# TPS_secondary_wiper.net
KiCad netlist of a schematic drawn in Altium Designer
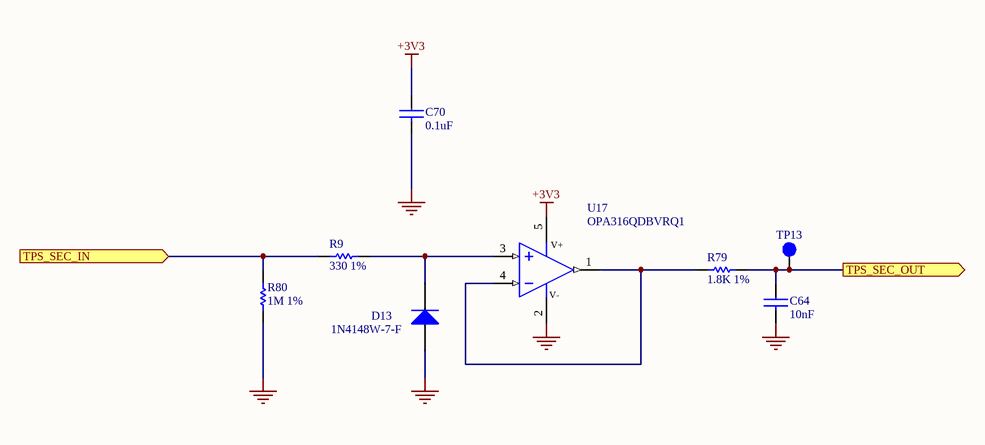
[diagram p0: TPS_secondary_wiper.SchDoc]

(export (version "E")
  (design (tool "Eeschema 10.0.6"))
  (components
    (comp (ref "C64")
      (value "10nF")
      (footprint "C0805")
      (fields
        (field (name "MANUFACTURER") "Yageo")
        (field (name "MANUFACTURER PART NUMBER") "CC0805KRX7R9BB103")
        (field (name "TOLERANCE") "10%")
      )
      (libsource (lib "MCx") (part "CC0805KRX7R9BB103"))
    )
    (comp (ref "C70")
      (value "0.1uF")
      (footprint "C0805")
      (description "Cap Ceramic 0.1uF 50V X7R 10% SMD 2.0 x 1.2 mm 125 C Paper T/R")
      (fields
        (field (name "MANUFACTURER") "KEMET")
        (field (name "MANUFACTURER PART NUMBER") "C0805C104K5RACTU")
      )
      (libsource (lib "MCx") (part "C0805C104K5RACTU"))
    )
    (comp (ref "D13")
      (value "1N4148W-7-F")
      (footprint "MC1:DIOD-SOD123-2_V")
      (description "DIODE GEN PURP 100V 300MA SOD123")
      (fields (field (name "MANUFACTURER") "Diodes") (field (name "VOLTAGE") "100V"))
      (libsource (lib "MC1") (part "1N4148W-7-F"))
    )
    (comp (ref "R9")
      (value "330 1%")
      (footprint "R0805")
      (description "RES SMD 330 OHM 1% 1/8W 0805")
      (fields
        (field (name "MANUFACTURER") "Panasonic")
        (field (name "MANUFACTURER PART NUMBER") "ERJ-6ENF3300V")
      )
      (libsource (lib "MCx") (part "ERJ-6ENF3300V"))
    )
    (comp (ref "R79")
      (value "1.8K 1%")
      (footprint "R0805")
      (description "RESISTOR, 0805, 0.125W, 1%, 1K8")
      (fields
        (field (name "MANUFACTURER") "Panasonic")
        (field (name "MANUFACTURER PART NUMBER") "ERJ-6ENF1801V")
      )
      (libsource (lib "MCx") (part "ERJ-6ENF1801V"))
    )
    (comp (ref "R80")
      (value "1M 1%")
      (footprint "R0805")
      (description "Res Thick Film 0805 1M Ohm 1% 1/8W 100ppm/C Molded SMD Punched Carrier T/R")
      (fields
        (field (name "MANUFACTURER") "Panasonic")
        (field (name "MANUFACTURER PART NUMBER") "ERJ-6ENF1004V")
      )
      (libsource (lib "MCx") (part "ERJ-6ENF1004V"))
    )
    (comp (ref "TP13")
      (value "T")
      (footprint "MC1:TESTPOINTSMD_1x1MM")
      (description "SMD Test Point")
      (libsource (lib "MC1") (part "TestPoint_SMD_1x1"))
    )
    (comp (ref "U17")
      (value "OPA316QDBVRQ1")
      (footprint "DBV0005A_M")
      (description "Op Amp Single Low Power Amplifier R-R I/O ±2.75V/5.5V Automotive 5-Pin SOT-23 T/R")
      (fields (field (name "MANUFACTURER") "Texas Instruments"))
      (libsource (lib "MCx") (part "OPA316QDBVRQ1"))
    )
  )
  (nets
    (net (code "1") (name "+3V3") (class "Default")
      (node (ref "C70") (pin "1") (pinfunction "1_1") (pintype "passive"))
      (node (ref "U17") (pin "5") (pinfunction "V+_5") (pintype "power_in"))
    )
    (net (code "2") (name "/TPS_SEC_IN") (class "Default")
      (node (ref "R80") (pin "2") (pinfunction "2_2") (pintype "passive"))
      (node (ref "R9") (pin "1") (pinfunction "1_1") (pintype "passive"))
    )
    (net (code "3") (name "/TPS_SEC_OUT") (class "Default")
      (node (ref "C64") (pin "1") (pinfunction "1_1") (pintype "passive"))
      (node (ref "R79") (pin "2") (pinfunction "2_2") (pintype "passive"))
      (node (ref "TP13") (pin "1") (pinfunction "1_1") (pintype "passive"))
    )
    (net (code "4") (name "GND") (class "Default")
      (node (ref "C64") (pin "2") (pinfunction "2_2") (pintype "passive"))
      (node (ref "C70") (pin "2") (pinfunction "2_2") (pintype "passive"))
      (node (ref "D13") (pin "1") (pinfunction "A_1") (pintype "passive"))
      (node (ref "R80") (pin "1") (pinfunction "1_1") (pintype "passive"))
      (node (ref "U17") (pin "2") (pinfunction "V-_2") (pintype "power_in"))
    )
    (net (code "5") (name "Net-(D13-K)") (class "Default")
      (node (ref "D13") (pin "2") (pinfunction "K_2") (pintype "passive"))
      (node (ref "R9") (pin "2") (pinfunction "2_2") (pintype "passive"))
      (node (ref "U17") (pin "3") (pinfunction "IN+_3") (pintype "input"))
    )
    (net (code "6") (name "Net-(U17-IN-)") (class "Default")
      (node (ref "R79") (pin "1") (pinfunction "1_1") (pintype "passive"))
      (node (ref "U17") (pin "1") (pinfunction "OUT_1") (pintype "output"))
      (node (ref "U17") (pin "4") (pinfunction "IN-_4") (pintype "input"))
    )
  )
)
